# Sensor.net
KiCad netlist of a schematic drawn in Altium Designer
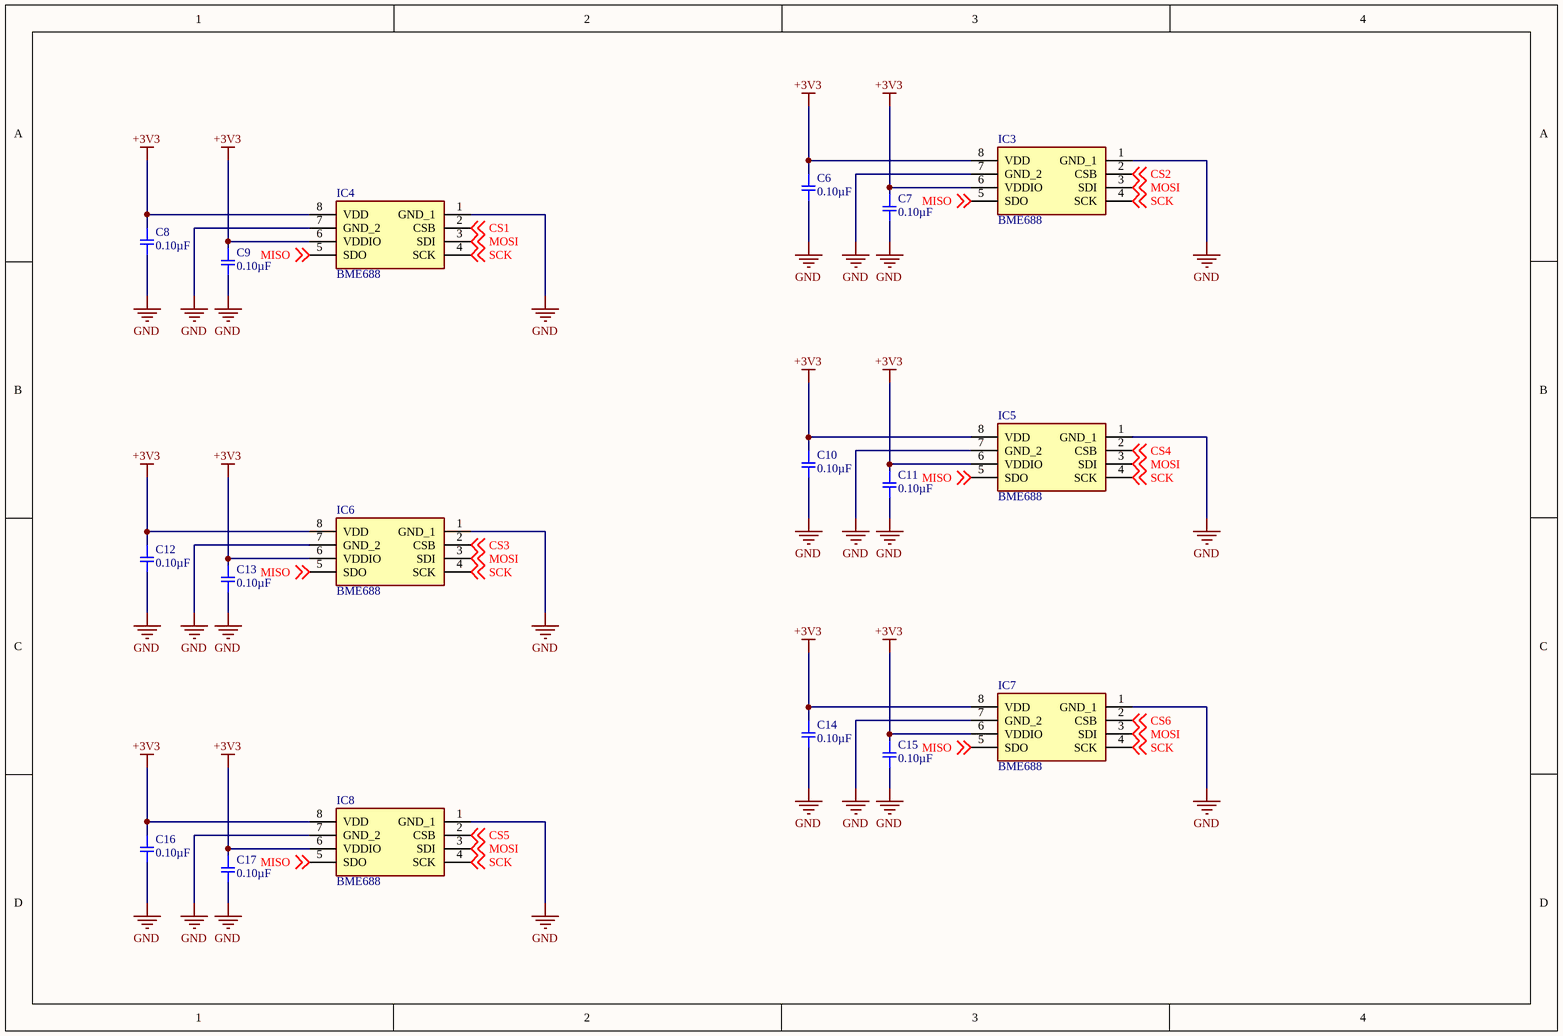
[diagram p0: Sensor.SchDoc]

(export (version "E")
  (design (tool "Eeschema 10.0.6"))
  (components
    (comp (ref "C6")
      (value "0.10µF")
      (footprint "SMD-0402C")
      (description "CAP CER 0.1UF 16V X7R 0402")
      (fields
        (field (name "DIGI-KEY PART NUMBER") "490-4759-1-ND")
        (field (name "PART NUMBER") "GCM155R71C104KA55D")
      )
      (libsource (lib "capacitor_murata_0402") (part "GCM155R71C104KA55D"))
    )
    (comp (ref "C7")
      (value "0.10µF")
      (footprint "SMD-0402C")
      (description "CAP CER 0.1UF 16V X7R 0402")
      (fields
        (field (name "DIGI-KEY PART NUMBER") "490-4759-1-ND")
        (field (name "PART NUMBER") "GCM155R71C104KA55D")
      )
      (libsource (lib "capacitor_murata_0402") (part "GCM155R71C104KA55D"))
    )
    (comp (ref "C8")
      (value "0.10µF")
      (footprint "SMD-0402C")
      (description "CAP CER 0.1UF 16V X7R 0402")
      (fields
        (field (name "DIGI-KEY PART NUMBER") "490-4759-1-ND")
        (field (name "PART NUMBER") "GCM155R71C104KA55D")
      )
      (libsource (lib "capacitor_murata_0402") (part "GCM155R71C104KA55D"))
    )
    (comp (ref "C9")
      (value "0.10µF")
      (footprint "SMD-0402C")
      (description "CAP CER 0.1UF 16V X7R 0402")
      (fields
        (field (name "DIGI-KEY PART NUMBER") "490-4759-1-ND")
        (field (name "PART NUMBER") "GCM155R71C104KA55D")
      )
      (libsource (lib "capacitor_murata_0402") (part "GCM155R71C104KA55D"))
    )
    (comp (ref "C10")
      (value "0.10µF")
      (footprint "SMD-0402C")
      (description "CAP CER 0.1UF 16V X7R 0402")
      (fields
        (field (name "DIGI-KEY PART NUMBER") "490-4759-1-ND")
        (field (name "PART NUMBER") "GCM155R71C104KA55D")
      )
      (libsource (lib "capacitor_murata_0402") (part "GCM155R71C104KA55D"))
    )
    (comp (ref "C11")
      (value "0.10µF")
      (footprint "SMD-0402C")
      (description "CAP CER 0.1UF 16V X7R 0402")
      (fields
        (field (name "DIGI-KEY PART NUMBER") "490-4759-1-ND")
        (field (name "PART NUMBER") "GCM155R71C104KA55D")
      )
      (libsource (lib "capacitor_murata_0402") (part "GCM155R71C104KA55D"))
    )
    (comp (ref "C12")
      (value "0.10µF")
      (footprint "SMD-0402C")
      (description "CAP CER 0.1UF 16V X7R 0402")
      (fields
        (field (name "DIGI-KEY PART NUMBER") "490-4759-1-ND")
        (field (name "PART NUMBER") "GCM155R71C104KA55D")
      )
      (libsource (lib "capacitor_murata_0402") (part "GCM155R71C104KA55D"))
    )
    (comp (ref "C13")
      (value "0.10µF")
      (footprint "SMD-0402C")
      (description "CAP CER 0.1UF 16V X7R 0402")
      (fields
        (field (name "DIGI-KEY PART NUMBER") "490-4759-1-ND")
        (field (name "PART NUMBER") "GCM155R71C104KA55D")
      )
      (libsource (lib "capacitor_murata_0402") (part "GCM155R71C104KA55D"))
    )
    (comp (ref "C14")
      (value "0.10µF")
      (footprint "SMD-0402C")
      (description "CAP CER 0.1UF 16V X7R 0402")
      (fields
        (field (name "DIGI-KEY PART NUMBER") "490-4759-1-ND")
        (field (name "PART NUMBER") "GCM155R71C104KA55D")
      )
      (libsource (lib "capacitor_murata_0402") (part "GCM155R71C104KA55D"))
    )
    (comp (ref "C15")
      (value "0.10µF")
      (footprint "SMD-0402C")
      (description "CAP CER 0.1UF 16V X7R 0402")
      (fields
        (field (name "DIGI-KEY PART NUMBER") "490-4759-1-ND")
        (field (name "PART NUMBER") "GCM155R71C104KA55D")
      )
      (libsource (lib "capacitor_murata_0402") (part "GCM155R71C104KA55D"))
    )
    (comp (ref "C16")
      (value "0.10µF")
      (footprint "SMD-0402C")
      (description "CAP CER 0.1UF 16V X7R 0402")
      (fields
        (field (name "DIGI-KEY PART NUMBER") "490-4759-1-ND")
        (field (name "PART NUMBER") "GCM155R71C104KA55D")
      )
      (libsource (lib "capacitor_murata_0402") (part "GCM155R71C104KA55D"))
    )
    (comp (ref "C17")
      (value "0.10µF")
      (footprint "SMD-0402C")
      (description "CAP CER 0.1UF 16V X7R 0402")
      (fields
        (field (name "DIGI-KEY PART NUMBER") "490-4759-1-ND")
        (field (name "PART NUMBER") "GCM155R71C104KA55D")
      )
      (libsource (lib "capacitor_murata_0402") (part "GCM155R71C104KA55D"))
    )
    (comp (ref "IC3")
      (value "BME688")
      (footprint "SamacSys:BME688")
      (description "Integrated Circuit")
      (fields (field (name "MOUSER PART NUMBER") "262-BME688"))
      (libsource (lib "*") (part "BME688"))
    )
    (comp (ref "IC4")
      (value "BME688")
      (footprint "SamacSys:BME688")
      (description "Integrated Circuit")
      (fields (field (name "MOUSER PART NUMBER") "262-BME688"))
      (libsource (lib "*") (part "BME688"))
    )
    (comp (ref "IC5")
      (value "BME688")
      (footprint "SamacSys:BME688")
      (description "Integrated Circuit")
      (fields (field (name "MOUSER PART NUMBER") "262-BME688"))
      (libsource (lib "*") (part "BME688"))
    )
    (comp (ref "IC6")
      (value "BME688")
      (footprint "SamacSys:BME688")
      (description "Integrated Circuit")
      (fields (field (name "MOUSER PART NUMBER") "262-BME688"))
      (libsource (lib "*") (part "BME688"))
    )
    (comp (ref "IC7")
      (value "BME688")
      (footprint "SamacSys:BME688")
      (description "Integrated Circuit")
      (fields (field (name "MOUSER PART NUMBER") "262-BME688"))
      (libsource (lib "*") (part "BME688"))
    )
    (comp (ref "IC8")
      (value "BME688")
      (footprint "SamacSys:BME688")
      (description "Integrated Circuit")
      (fields (field (name "MOUSER PART NUMBER") "262-BME688"))
      (libsource (lib "*") (part "BME688"))
    )
  )
  (nets
    (net (code "1") (name "+3V3") (class "Default")
      (node (ref "C10") (pin "1") (pinfunction "1_1") (pintype "passive"))
      (node (ref "C11") (pin "1") (pinfunction "1_1") (pintype "passive"))
      (node (ref "C12") (pin "1") (pinfunction "1_1") (pintype "passive"))
      (node (ref "C13") (pin "1") (pinfunction "1_1") (pintype "passive"))
      (node (ref "C14") (pin "1") (pinfunction "1_1") (pintype "passive"))
      (node (ref "C15") (pin "1") (pinfunction "1_1") (pintype "passive"))
      (node (ref "C16") (pin "1") (pinfunction "1_1") (pintype "passive"))
      (node (ref "C17") (pin "1") (pinfunction "1_1") (pintype "passive"))
      (node (ref "C6") (pin "1") (pinfunction "1_1") (pintype "passive"))
      (node (ref "C7") (pin "1") (pinfunction "1_1") (pintype "passive"))
      (node (ref "C8") (pin "1") (pinfunction "1_1") (pintype "passive"))
      (node (ref "C9") (pin "1") (pinfunction "1_1") (pintype "passive"))
      (node (ref "IC3") (pin "6") (pinfunction "VDDIO_6") (pintype "passive"))
      (node (ref "IC3") (pin "8") (pinfunction "VDD_8") (pintype "passive"))
      (node (ref "IC4") (pin "6") (pinfunction "VDDIO_6") (pintype "passive"))
      (node (ref "IC4") (pin "8") (pinfunction "VDD_8") (pintype "passive"))
      (node (ref "IC5") (pin "6") (pinfunction "VDDIO_6") (pintype "passive"))
      (node (ref "IC5") (pin "8") (pinfunction "VDD_8") (pintype "passive"))
      (node (ref "IC6") (pin "6") (pinfunction "VDDIO_6") (pintype "passive"))
      (node (ref "IC6") (pin "8") (pinfunction "VDD_8") (pintype "passive"))
      (node (ref "IC7") (pin "6") (pinfunction "VDDIO_6") (pintype "passive"))
      (node (ref "IC7") (pin "8") (pinfunction "VDD_8") (pintype "passive"))
      (node (ref "IC8") (pin "6") (pinfunction "VDDIO_6") (pintype "passive"))
      (node (ref "IC8") (pin "8") (pinfunction "VDD_8") (pintype "passive"))
    )
    (net (code "2") (name "CS1") (class "Default")
      (node (ref "IC4") (pin "2") (pinfunction "CSB_2") (pintype "passive"))
    )
    (net (code "3") (name "CS2") (class "Default")
      (node (ref "IC3") (pin "2") (pinfunction "CSB_2") (pintype "passive"))
    )
    (net (code "4") (name "CS3") (class "Default")
      (node (ref "IC6") (pin "2") (pinfunction "CSB_2") (pintype "passive"))
    )
    (net (code "5") (name "CS4") (class "Default")
      (node (ref "IC5") (pin "2") (pinfunction "CSB_2") (pintype "passive"))
    )
    (net (code "6") (name "CS5") (class "Default")
      (node (ref "IC8") (pin "2") (pinfunction "CSB_2") (pintype "passive"))
    )
    (net (code "7") (name "CS6") (class "Default")
      (node (ref "IC7") (pin "2") (pinfunction "CSB_2") (pintype "passive"))
    )
    (net (code "8") (name "GND") (class "Default")
      (node (ref "C10") (pin "2") (pinfunction "2_2") (pintype "passive"))
      (node (ref "C11") (pin "2") (pinfunction "2_2") (pintype "passive"))
      (node (ref "C12") (pin "2") (pinfunction "2_2") (pintype "passive"))
      (node (ref "C13") (pin "2") (pinfunction "2_2") (pintype "passive"))
      (node (ref "C14") (pin "2") (pinfunction "2_2") (pintype "passive"))
      (node (ref "C15") (pin "2") (pinfunction "2_2") (pintype "passive"))
      (node (ref "C16") (pin "2") (pinfunction "2_2") (pintype "passive"))
      (node (ref "C17") (pin "2") (pinfunction "2_2") (pintype "passive"))
      (node (ref "C6") (pin "2") (pinfunction "2_2") (pintype "passive"))
      (node (ref "C7") (pin "2") (pinfunction "2_2") (pintype "passive"))
      (node (ref "C8") (pin "2") (pinfunction "2_2") (pintype "passive"))
      (node (ref "C9") (pin "2") (pinfunction "2_2") (pintype "passive"))
      (node (ref "IC3") (pin "1") (pinfunction "GND_1_1") (pintype "passive"))
      (node (ref "IC3") (pin "7") (pinfunction "GND_2_7") (pintype "passive"))
      (node (ref "IC4") (pin "1") (pinfunction "GND_1_1") (pintype "passive"))
      (node (ref "IC4") (pin "7") (pinfunction "GND_2_7") (pintype "passive"))
      (node (ref "IC5") (pin "1") (pinfunction "GND_1_1") (pintype "passive"))
      (node (ref "IC5") (pin "7") (pinfunction "GND_2_7") (pintype "passive"))
      (node (ref "IC6") (pin "1") (pinfunction "GND_1_1") (pintype "passive"))
      (node (ref "IC6") (pin "7") (pinfunction "GND_2_7") (pintype "passive"))
      (node (ref "IC7") (pin "1") (pinfunction "GND_1_1") (pintype "passive"))
      (node (ref "IC7") (pin "7") (pinfunction "GND_2_7") (pintype "passive"))
      (node (ref "IC8") (pin "1") (pinfunction "GND_1_1") (pintype "passive"))
      (node (ref "IC8") (pin "7") (pinfunction "GND_2_7") (pintype "passive"))
    )
    (net (code "9") (name "MISO") (class "Default")
      (node (ref "IC3") (pin "5") (pinfunction "SDO_5") (pintype "passive"))
      (node (ref "IC4") (pin "5") (pinfunction "SDO_5") (pintype "passive"))
      (node (ref "IC5") (pin "5") (pinfunction "SDO_5") (pintype "passive"))
      (node (ref "IC6") (pin "5") (pinfunction "SDO_5") (pintype "passive"))
      (node (ref "IC7") (pin "5") (pinfunction "SDO_5") (pintype "passive"))
      (node (ref "IC8") (pin "5") (pinfunction "SDO_5") (pintype "passive"))
    )
    (net (code "10") (name "MOSI") (class "Default")
      (node (ref "IC3") (pin "3") (pinfunction "SDI_3") (pintype "passive"))
      (node (ref "IC4") (pin "3") (pinfunction "SDI_3") (pintype "passive"))
      (node (ref "IC5") (pin "3") (pinfunction "SDI_3") (pintype "passive"))
      (node (ref "IC6") (pin "3") (pinfunction "SDI_3") (pintype "passive"))
      (node (ref "IC7") (pin "3") (pinfunction "SDI_3") (pintype "passive"))
      (node (ref "IC8") (pin "3") (pinfunction "SDI_3") (pintype "passive"))
    )
    (net (code "11") (name "SCK") (class "Default")
      (node (ref "IC3") (pin "4") (pinfunction "SCK_4") (pintype "passive"))
      (node (ref "IC4") (pin "4") (pinfunction "SCK_4") (pintype "passive"))
      (node (ref "IC5") (pin "4") (pinfunction "SCK_4") (pintype "passive"))
      (node (ref "IC6") (pin "4") (pinfunction "SCK_4") (pintype "passive"))
      (node (ref "IC7") (pin "4") (pinfunction "SCK_4") (pintype "passive"))
      (node (ref "IC8") (pin "4") (pinfunction "SCK_4") (pintype "passive"))
    )
  )
)
